# ESD_PROTECTION.net
KiCad netlist of a schematic drawn in Altium Designer
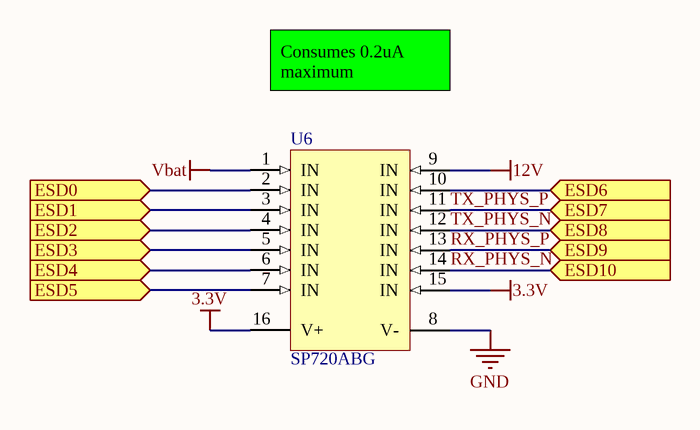
[diagram p0: ESD_PROTECTION.SchDoc]

(export (version "E")
  (design (tool "Eeschema 10.0.6"))
  (components
    (comp (ref "U6")
      (value "SP720ABG")
      (footprint "LFUS-SOIC-16_L")
      (fields (field (name "MANUFACTURER") "Littelfuse"))
      (libsource (lib "Altium Content Vault") (part "LFUS-SP720ABG-SOIC-16"))
    )
  )
  (nets
    (net (code "1") (name "/ESD0") (class "Default")
      (node (ref "U6") (pin "2") (pinfunction "IN_2") (pintype "input"))
    )
    (net (code "2") (name "/ESD1") (class "Default")
      (node (ref "U6") (pin "3") (pinfunction "IN_3") (pintype "input"))
    )
    (net (code "3") (name "/ESD2") (class "Default")
      (node (ref "U6") (pin "4") (pinfunction "IN_4") (pintype "input"))
    )
    (net (code "4") (name "/ESD3") (class "Default")
      (node (ref "U6") (pin "5") (pinfunction "IN_5") (pintype "input"))
    )
    (net (code "5") (name "/ESD4") (class "Default")
      (node (ref "U6") (pin "6") (pinfunction "IN_6") (pintype "input"))
    )
    (net (code "6") (name "/ESD5") (class "Default")
      (node (ref "U6") (pin "7") (pinfunction "IN_7") (pintype "input"))
    )
    (net (code "7") (name "/ESD6") (class "Default")
      (node (ref "U6") (pin "10") (pinfunction "IN_10") (pintype "input"))
    )
    (net (code "8") (name "/RX_PHYS_N") (class "Default")
      (node (ref "U6") (pin "14") (pinfunction "IN_14") (pintype "input"))
    )
    (net (code "9") (name "/RX_PHYS_P") (class "Default")
      (node (ref "U6") (pin "13") (pinfunction "IN_13") (pintype "input"))
    )
    (net (code "10") (name "/TX_PHYS_N") (class "Default")
      (node (ref "U6") (pin "12") (pinfunction "IN_12") (pintype "input"))
    )
    (net (code "11") (name "/TX_PHYS_P") (class "Default")
      (node (ref "U6") (pin "11") (pinfunction "IN_11") (pintype "input"))
    )
    (net (code "12") (name "3.3V") (class "Default")
      (node (ref "U6") (pin "15") (pinfunction "IN_15") (pintype "input"))
      (node (ref "U6") (pin "16") (pinfunction "V+_16") (pintype "power_in"))
    )
    (net (code "13") (name "12V") (class "Default")
      (node (ref "U6") (pin "9") (pinfunction "IN_9") (pintype "input"))
    )
    (net (code "14") (name "GND") (class "Default")
      (node (ref "U6") (pin "8") (pinfunction "V-_8") (pintype "power_in"))
    )
    (net (code "15") (name "Vbat") (class "Default")
      (node (ref "U6") (pin "1") (pinfunction "IN_1") (pintype "input"))
    )
  )
)
